# comunicacao.net
KiCad netlist of a schematic drawn in Altium Designer
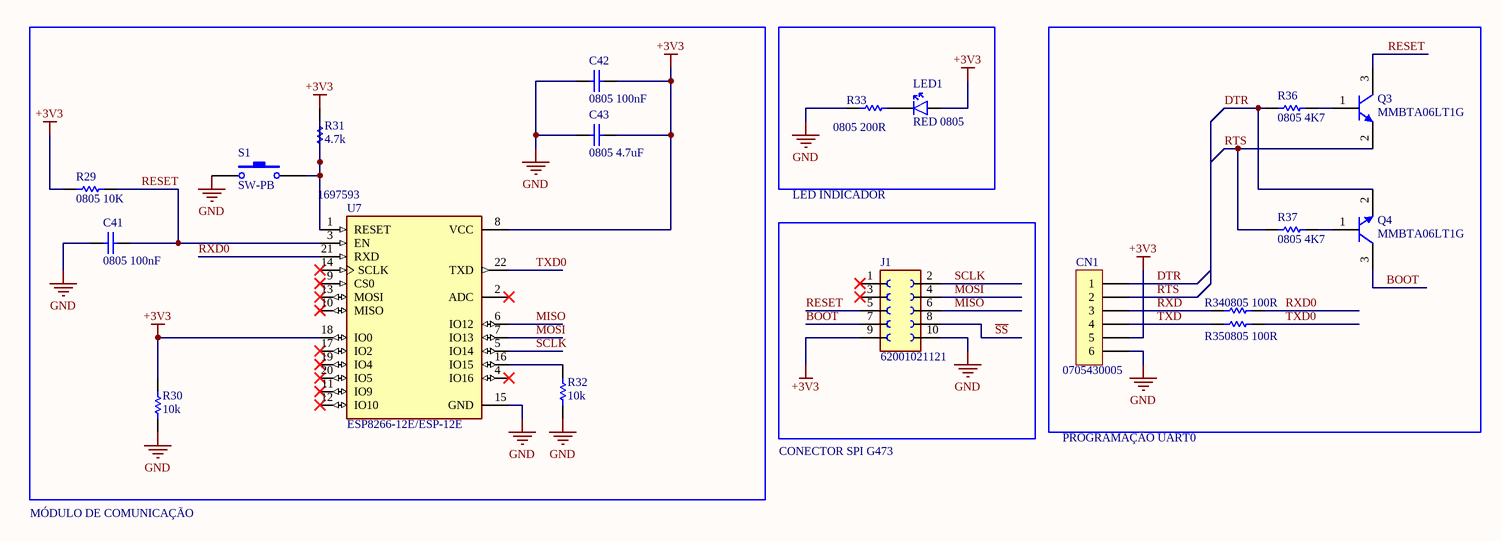
[diagram p0: comunicacao.SchDoc]

(export (version "E")
  (design (tool "Eeschema 10.0.6"))
  (components
    (comp (ref "C41")
      (value "0805 100nF")
      (footprint "CAP0805")
      (description "CC Series 0805 0.1 uF 50 V ±10 % Tolerance X7R SMT Multilayer Ceramic Capacitor")
      (fields
        (field (name "MANUFACTURER") "Yageo")
        (field (name "MANUFACTURER PART NUMBER") "CC0805KRX7R9BB104")
      )
      (libsource (lib "occhi") (part "CC0805KRX7R9BB104"))
    )
    (comp (ref "C42")
      (value "0805 100nF")
      (footprint "CAP0805")
      (description "CC Series 0805 0.1 uF 50 V ±10 % Tolerance X7R SMT Multilayer Ceramic Capacitor")
      (fields
        (field (name "MANUFACTURER") "Yageo")
        (field (name "MANUFACTURER PART NUMBER") "CC0805KRX7R9BB104")
      )
      (libsource (lib "occhi") (part "CC0805KRX7R9BB104"))
    )
    (comp (ref "C43")
      (value "0805 4.7uF")
      (footprint "CAP0805")
      (description "4.7uF ±10% 50V 0805")
      (fields
        (field (name "MANUFACTURER") "TDK")
        (field (name "MANUFACTURER PART NUMBER") "C2012X5R1H475K125AB")
      )
      (libsource (lib "occhi") (part "C2012X5R1H475K125AB"))
    )
    (comp (ref "CN1")
      (value "0705430005")
      (footprint "FP-0705430005-MFG")
      (description "Conn Shrouded Header (4 Sides) HDR 6 POS 2.54mm Solder ST Top Entry Thru-Hole SL™ Tube")
      (fields (field (name "MANUFACTURER") "Molex"))
      (libsource (lib "occhi") (part "0705430005"))
    )
    (comp (ref "J1")
      (value "62001021121")
      (footprint "62001021121")
      (fields (field (name "MF") "WÃ¼rth Elektronik"))
      (libsource (lib "62001021121") (part "62001021121"))
    )
    (comp (ref "LED1")
      (value "RED 0805")
      (footprint "LEDC2012X80N")
      (description "Red SMD 625nm LED Indication - Discrete 2V 0805 (2012 Metric)")
      (fields
        (field (name "MANUFACTURER_PART_NUMBER") "150080RS75000")
        (field (name "MOUSER PART NUMBER") "710-150080RS75000")
      )
      (libsource (lib "occhi") (part "150080RS75000"))
    )
    (comp (ref "Q3")
      (value "MMBTA06LT1G")
      (footprint "ONSC-SOT-23-3-318-08_V")
      (description "Trans GP BJT NPN 80V 0.5A 3-Pin SOT-23 T/R")
      (fields (field (name "MANUFACTURER") "ON Semiconductor"))
      (libsource (lib "occhi") (part "MMBTA06LT1G"))
    )
    (comp (ref "Q4")
      (value "MMBTA06LT1G")
      (footprint "ONSC-SOT-23-3-318-08_V")
      (description "Trans GP BJT NPN 80V 0.5A 3-Pin SOT-23 T/R")
      (fields (field (name "MANUFACTURER") "ON Semiconductor"))
      (libsource (lib "occhi") (part "MMBTA06LT1G"))
    )
    (comp (ref "R29")
      (value "0805 10K")
      (footprint "RES0805")
      (description "10K Omhs 0805 ± 1.00% 0.125W ± 100ppm/℃")
      (fields
        (field (name "MANUFACTURER") "Yageo")
        (field (name "MANUFACTURER PART NUMBER") "RC0603FR-0710KL")
      )
      (libsource (lib "occhi") (part "RC0805FR-0710KL"))
    )
    (comp (ref "R30")
      (value "10k")
      (footprint "R1608[0603]")
      (description "Res, 10K, 0.01%, 0.25W, 1206, Metal Foil")
      (fields (field (name "MANUFACTURER PART NUMBER") "Y163010K0000T9R") (field (name "TOLERANCE") "0.01%"))
      (libsource (lib "Basic Library") (part "R"))
    )
    (comp (ref "R31")
      (value "4.7k")
      (footprint "R1005[0402]")
      (description "Res Thick Film 1206 4.7K Ohm 5% 1/4W ±200ppm/°C Molded SMD Punched Carrier T/R")
      (fields (field (name "MANUFACTURER PART NUMBER") "ERJ-8GEYJ472V") (field (name "TOLERANCE") "5%"))
      (libsource (lib "Basic Library") (part "R"))
    )
    (comp (ref "R32")
      (value "10k")
      (footprint "R1608[0603]")
      (description "Res, 10K, 0.01%, 0.25W, 1206, Metal Foil")
      (fields (field (name "MANUFACTURER PART NUMBER") "Y163010K0000T9R") (field (name "TOLERANCE") "0.01%"))
      (libsource (lib "Basic Library") (part "R"))
    )
    (comp (ref "R33")
      (value "0805 200R")
      (footprint "RES0805")
      (description "200 Ohm  0805 ± 1.00% 0.125W ± 100ppm/℃")
      (fields
        (field (name "MANUFACTURER") "Yageo")
        (field (name "MANUFACTURER PART NUMBER") "RC0603FR-07200RL")
      )
      (libsource (lib "occhi") (part "RC0805FR-07200RL"))
    )
    (comp (ref "R34")
      (value "0805 100R")
      (footprint "RES0805")
      (description "100R ± 1.00% 0.125W ± 100ppm/℃ 0805")
      (fields
        (field (name "MANUFACTURER") "Yageo")
        (field (name "MANUFACTURER PART NUMBER") "RC0805FR-07100RL")
      )
      (libsource (lib "occhi") (part "RC0805FR-07100RL"))
    )
    (comp (ref "R35")
      (value "0805 100R")
      (footprint "RES0805")
      (description "100R ± 1.00% 0.125W ± 100ppm/℃ 0805")
      (fields
        (field (name "MANUFACTURER") "Yageo")
        (field (name "MANUFACTURER PART NUMBER") "RC0805FR-07100RL")
      )
      (libsource (lib "occhi") (part "RC0805FR-07100RL"))
    )
    (comp (ref "R36")
      (value "0805 4K7")
      (footprint "RES0805")
      (description "4700Ω ± 1.00% 0.125W ± 100ppm/℃ 0805")
      (fields
        (field (name "MANUFACTURER") "Yageo")
        (field (name "MANUFACTURER PART NUMBER") "RC0805FR-074K7L")
      )
      (libsource (lib "occhi") (part "RC0805FR-074K7L"))
    )
    (comp (ref "R37")
      (value "0805 4K7")
      (footprint "RES0805")
      (description "4700Ω ± 1.00% 0.125W ± 100ppm/℃ 0805")
      (fields
        (field (name "MANUFACTURER") "Yageo")
        (field (name "MANUFACTURER PART NUMBER") "RC0805FR-074K7L")
      )
      (libsource (lib "occhi") (part "RC0805FR-074K7L"))
    )
    (comp (ref "S1")
      (value "SW-PB")
      (footprint "PB-SW")
      (description "Tactile Switch")
      (libsource (lib "Basic Library") (part "SW Tact"))
    )
    (comp (ref "U7")
      (value "ESP8266-12E/ESP-12E")
      (footprint "XCVR_ESP8266-12E/ESP-12E")
      (fields (field (name "MF") "AI-Thinker") (field (name "SUPPLIER PART NUMBER 1") "1697593"))
      (libsource (lib "ESP8266-12E_ESP-12E") (part "ESP8266-12E/ESP-12E"))
    )
  )
  (nets
    (net (code "1") (name "+3V3") (class "Default")
      (node (ref "C42") (pin "2") (pinfunction "2_2") (pintype "passive"))
      (node (ref "C43") (pin "2") (pinfunction "2_2") (pintype "passive"))
      (node (ref "CN1") (pin "5") (pinfunction "5_5") (pintype "passive"))
      (node (ref "J1") (pin "9") (pinfunction "5_9") (pintype "passive"))
      (node (ref "LED1") (pin "2") (pinfunction "A_2") (pintype "passive"))
      (node (ref "R29") (pin "1") (pinfunction "1_1") (pintype "passive"))
      (node (ref "R30") (pin "2") (pinfunction "2_2") (pintype "passive"))
      (node (ref "R31") (pin "2") (pinfunction "2_2") (pintype "passive"))
      (node (ref "U7") (pin "18") (pinfunction "IO0_18") (pintype "bidirectional"))
      (node (ref "U7") (pin "8") (pinfunction "VCC_8") (pintype "power_in"))
    )
    (net (code "2") (name "/BOOT") (class "Default")
      (node (ref "J1") (pin "7") (pinfunction "4_7") (pintype "passive"))
      (node (ref "Q4") (pin "3") (pinfunction "C_3") (pintype "passive"))
    )
    (net (code "3") (name "/DTR") (class "Default")
      (node (ref "CN1") (pin "1") (pinfunction "1_1") (pintype "passive"))
      (node (ref "Q4") (pin "2") (pinfunction "E_2") (pintype "passive"))
      (node (ref "R36") (pin "1") (pinfunction "1_1") (pintype "passive"))
    )
    (net (code "4") (name "/MISO") (class "Default")
      (node (ref "J1") (pin "6") (pinfunction "8_6") (pintype "passive"))
      (node (ref "U7") (pin "6") (pinfunction "IO12_6") (pintype "bidirectional"))
    )
    (net (code "5") (name "/MOSI") (class "Default")
      (node (ref "J1") (pin "4") (pinfunction "9_4") (pintype "passive"))
      (node (ref "U7") (pin "7") (pinfunction "IO13_7") (pintype "bidirectional"))
    )
    (net (code "6") (name "/RESET") (class "Default")
      (node (ref "C41") (pin "2") (pinfunction "2_2") (pintype "passive"))
      (node (ref "J1") (pin "5") (pinfunction "3_5") (pintype "passive"))
      (node (ref "Q3") (pin "3") (pinfunction "C_3") (pintype "passive"))
      (node (ref "R29") (pin "2") (pinfunction "2_2") (pintype "passive"))
      (node (ref "U7") (pin "3") (pinfunction "EN_3") (pintype "input"))
    )
    (net (code "7") (name "/RTS") (class "Default")
      (node (ref "CN1") (pin "2") (pinfunction "2_2") (pintype "passive"))
      (node (ref "Q3") (pin "2") (pinfunction "E_2") (pintype "passive"))
      (node (ref "R37") (pin "1") (pinfunction "1_1") (pintype "passive"))
    )
    (net (code "8") (name "/RXD") (class "Default")
      (node (ref "CN1") (pin "3") (pinfunction "3_3") (pintype "passive"))
      (node (ref "R34") (pin "1") (pinfunction "1_1") (pintype "passive"))
    )
    (net (code "9") (name "/RXD0") (class "Default")
      (node (ref "R34") (pin "2") (pinfunction "2_2") (pintype "passive"))
      (node (ref "U7") (pin "21") (pinfunction "RXD_21") (pintype "input"))
    )
    (net (code "10") (name "/SCLK") (class "Default")
      (node (ref "J1") (pin "2") (pinfunction "10_2") (pintype "passive"))
      (node (ref "U7") (pin "5") (pinfunction "IO14_5") (pintype "bidirectional"))
    )
    (net (code "11") (name "/TXD") (class "Default")
      (node (ref "CN1") (pin "4") (pinfunction "4_4") (pintype "passive"))
      (node (ref "R35") (pin "1") (pinfunction "1_1") (pintype "passive"))
    )
    (net (code "12") (name "/TXD0") (class "Default")
      (node (ref "R35") (pin "2") (pinfunction "2_2") (pintype "passive"))
      (node (ref "U7") (pin "22") (pinfunction "TXD_22") (pintype "output"))
    )
    (net (code "13") (name "/~{SS}") (class "Default")
      (node (ref "J1") (pin "8") (pinfunction "7_8") (pintype "passive"))
    )
    (net (code "14") (name "GND") (class "Default")
      (node (ref "C41") (pin "1") (pinfunction "1_1") (pintype "passive"))
      (node (ref "C42") (pin "1") (pinfunction "1_1") (pintype "passive"))
      (node (ref "C43") (pin "1") (pinfunction "1_1") (pintype "passive"))
      (node (ref "CN1") (pin "6") (pinfunction "6_6") (pintype "passive"))
      (node (ref "J1") (pin "10") (pinfunction "6_10") (pintype "passive"))
      (node (ref "R30") (pin "1") (pinfunction "1_1") (pintype "passive"))
      (node (ref "R32") (pin "1") (pinfunction "1_1") (pintype "passive"))
      (node (ref "R33") (pin "1") (pinfunction "1_1") (pintype "passive"))
      (node (ref "S1") (pin "1") (pinfunction "1_1") (pintype "passive"))
      (node (ref "U7") (pin "15") (pinfunction "GND_15") (pintype "power_in"))
    )
    (net (code "15") (name "Net-(LED1-K)") (class "Default")
      (node (ref "LED1") (pin "1") (pinfunction "K_1") (pintype "passive"))
      (node (ref "R33") (pin "2") (pinfunction "2_2") (pintype "passive"))
    )
    (net (code "16") (name "Net-(Q3-B)") (class "Default")
      (node (ref "Q3") (pin "1") (pinfunction "B_1") (pintype "passive"))
      (node (ref "R36") (pin "2") (pinfunction "2_2") (pintype "passive"))
    )
    (net (code "17") (name "Net-(Q4-B)") (class "Default")
      (node (ref "Q4") (pin "1") (pinfunction "B_1") (pintype "passive"))
      (node (ref "R37") (pin "2") (pinfunction "2_2") (pintype "passive"))
    )
    (net (code "18") (name "Net-(U7-IO15)") (class "Default")
      (node (ref "R32") (pin "2") (pinfunction "2_2") (pintype "passive"))
      (node (ref "U7") (pin "16") (pinfunction "IO15_16") (pintype "bidirectional"))
    )
    (net (code "19") (name "Net-(U7-RESET)") (class "Default")
      (node (ref "R31") (pin "1") (pinfunction "1_1") (pintype "passive"))
      (node (ref "S1") (pin "2") (pinfunction "2_2") (pintype "passive"))
      (node (ref "U7") (pin "1") (pinfunction "RESET_1") (pintype "input"))
    )
    (net (code "20") (name "unconnected-(J1-2-Pad3)") (class "Default")
      (node (ref "J1") (pin "3") (pinfunction "2_3") (pintype "passive+no_connect"))
    )
    (net (code "21") (name "unconnected-(J1-Pad1)") (class "Default")
      (node (ref "J1") (pin "1") (pinfunction "1_1") (pintype "passive+no_connect"))
    )
    (net (code "22") (name "unconnected-(U7-ADC-Pad2)") (class "Default")
      (node (ref "U7") (pin "2") (pinfunction "ADC_2") (pintype "passive+no_connect"))
    )
    (net (code "23") (name "unconnected-(U7-CS0-Pad9)") (class "Default")
      (node (ref "U7") (pin "9") (pinfunction "CS0_9") (pintype "input+no_connect"))
    )
    (net (code "24") (name "unconnected-(U7-IO2-Pad17)") (class "Default")
      (node (ref "U7") (pin "17") (pinfunction "IO2_17") (pintype "bidirectional+no_connect"))
    )
    (net (code "25") (name "unconnected-(U7-IO4-Pad19)") (class "Default")
      (node (ref "U7") (pin "19") (pinfunction "IO4_19") (pintype "bidirectional+no_connect"))
    )
    (net (code "26") (name "unconnected-(U7-IO5-Pad20)") (class "Default")
      (node (ref "U7") (pin "20") (pinfunction "IO5_20") (pintype "bidirectional+no_connect"))
    )
    (net (code "27") (name "unconnected-(U7-IO9-Pad11)") (class "Default")
      (node (ref "U7") (pin "11") (pinfunction "IO9_11") (pintype "bidirectional+no_connect"))
    )
    (net (code "28") (name "unconnected-(U7-IO10-Pad12)") (class "Default")
      (node (ref "U7") (pin "12") (pinfunction "IO10_12") (pintype "bidirectional+no_connect"))
    )
    (net (code "29") (name "unconnected-(U7-IO16-Pad4)") (class "Default")
      (node (ref "U7") (pin "4") (pinfunction "IO16_4") (pintype "bidirectional+no_connect"))
    )
    (net (code "30") (name "unconnected-(U7-MISO-Pad10)") (class "Default")
      (node (ref "U7") (pin "10") (pinfunction "MISO_10") (pintype "bidirectional+no_connect"))
    )
    (net (code "31") (name "unconnected-(U7-MOSI-Pad13)") (class "Default")
      (node (ref "U7") (pin "13") (pinfunction "MOSI_13") (pintype "bidirectional+no_connect"))
    )
    (net (code "32") (name "unconnected-(U7-SCLK-Pad14)") (class "Default")
      (node (ref "U7") (pin "14") (pinfunction "SCLK_14") (pintype "input+no_connect"))
    )
  )
)
